# pcb_balun_bottom_notch.net
KiCad netlist of a schematic drawn in EAGLE
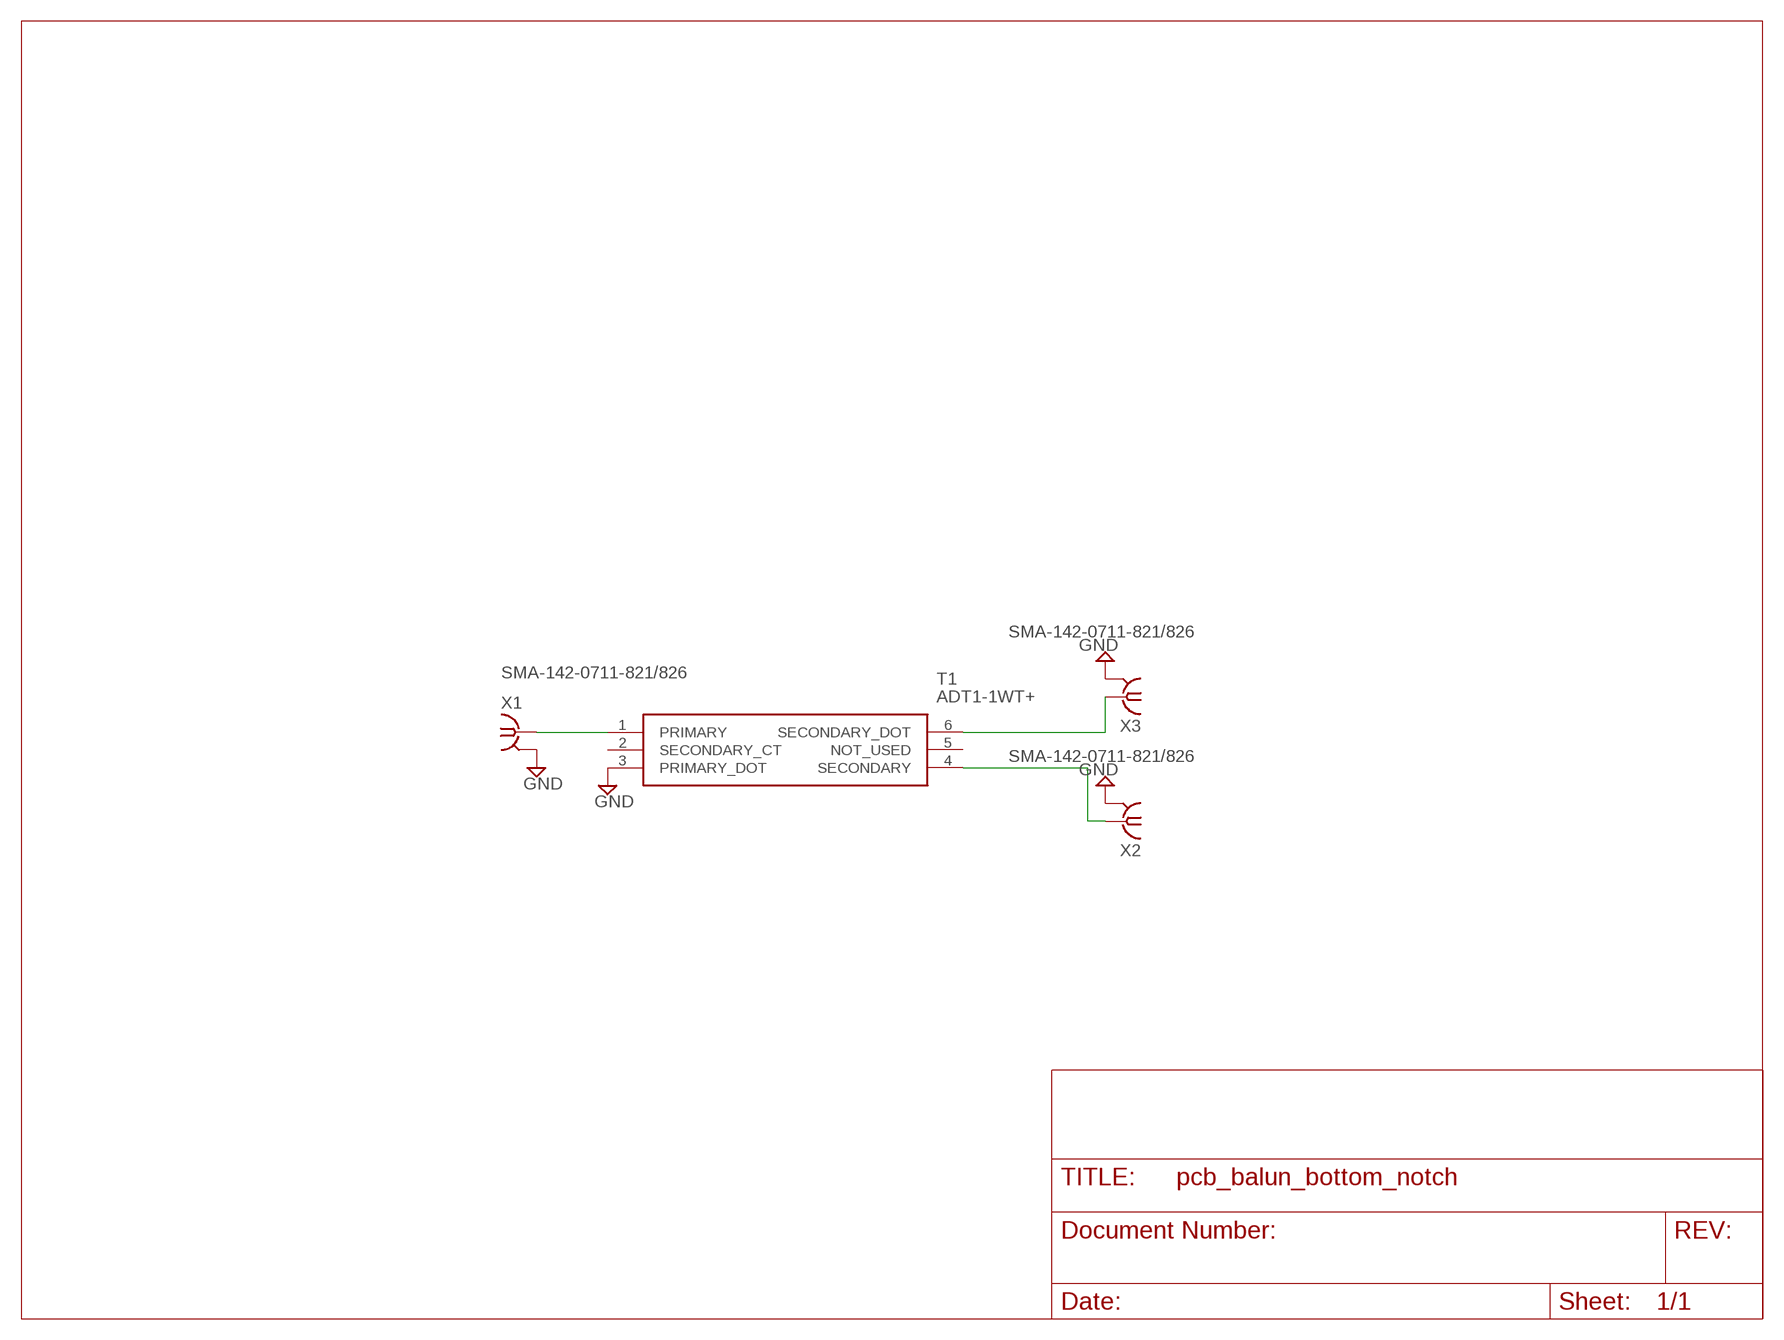
[diagram p0: schematic, sheet 1]

(export (version "E")
  (design (tool "Eeschema 10.0.6"))
  (components
    (comp (ref "T1")
      (value "ADT1-1WT+")
      (footprint "eagle-import:ADT11WT")
      (fields (field (name "MOUSER_PART_NUMBER") "139-ADT1-1WT"))
      (libsource (lib "eagle-import") (part "ADT1-1WT+"))
    )
    (comp (ref "X1")
      (value "SMA-142-0711-821/826")
      (footprint "eagle-import:J502-ND-142-0711-821_826")
      (fields (field (name "MF") "JOHNSON COMPONENTS") (field (name "MPN") "142-0711-821"))
      (libsource (lib "eagle-import") (part "SMA-142-0711-821/826"))
    )
    (comp (ref "X2")
      (value "SMA-142-0711-821/826")
      (footprint "eagle-import:J502-ND-142-0711-821_826")
      (fields (field (name "MF") "JOHNSON COMPONENTS") (field (name "MPN") "142-0711-821"))
      (libsource (lib "eagle-import") (part "SMA-142-0711-821/826"))
    )
    (comp (ref "X3")
      (value "SMA-142-0711-821/826")
      (footprint "eagle-import:J502-ND-142-0711-821_826")
      (fields (field (name "MF") "JOHNSON COMPONENTS") (field (name "MPN") "142-0711-821"))
      (libsource (lib "eagle-import") (part "SMA-142-0711-821/826"))
    )
  )
  (nets
    (net (code "1") (name "GND") (class "Default")
      (node (ref "T1") (pin "3") (pinfunction "PRIMARY_DOT_3") (pintype "bidirectional"))
      (node (ref "X1") (pin "G@1") (pinfunction "2_G@1") (pintype "passive"))
      (node (ref "X1") (pin "G@2") (pinfunction "2_G@2") (pintype "passive"))
      (node (ref "X1") (pin "G@3") (pinfunction "2_G@3") (pintype "passive"))
      (node (ref "X1") (pin "G@4") (pinfunction "2_G@4") (pintype "passive"))
      (node (ref "X2") (pin "G@1") (pinfunction "2_G@1") (pintype "passive"))
      (node (ref "X2") (pin "G@2") (pinfunction "2_G@2") (pintype "passive"))
      (node (ref "X2") (pin "G@3") (pinfunction "2_G@3") (pintype "passive"))
      (node (ref "X2") (pin "G@4") (pinfunction "2_G@4") (pintype "passive"))
      (node (ref "X3") (pin "G@1") (pinfunction "2_G@1") (pintype "passive"))
      (node (ref "X3") (pin "G@2") (pinfunction "2_G@2") (pintype "passive"))
      (node (ref "X3") (pin "G@3") (pinfunction "2_G@3") (pintype "passive"))
      (node (ref "X3") (pin "G@4") (pinfunction "2_G@4") (pintype "passive"))
    )
    (net (code "2") (name "Net-(T1-PRIMARY)") (class "Default")
      (node (ref "T1") (pin "1") (pinfunction "PRIMARY_1") (pintype "bidirectional"))
      (node (ref "X1") (pin "1") (pinfunction "1_1") (pintype "passive"))
    )
    (net (code "3") (name "Net-(T1-SECONDARY)") (class "Default")
      (node (ref "T1") (pin "4") (pinfunction "SECONDARY_4") (pintype "bidirectional"))
      (node (ref "X2") (pin "1") (pinfunction "1_1") (pintype "passive"))
    )
    (net (code "4") (name "Net-(T1-SECONDARY_DOT)") (class "Default")
      (node (ref "T1") (pin "6") (pinfunction "SECONDARY_DOT_6") (pintype "bidirectional"))
      (node (ref "X3") (pin "1") (pinfunction "1_1") (pintype "passive"))
    )
    (net (code "5") (name "unconnected-(T1-NOT_USED-Pad5)") (class "Default")
      (node (ref "T1") (pin "5") (pinfunction "NOT_USED_5") (pintype "bidirectional"))
    )
    (net (code "6") (name "unconnected-(T1-SECONDARY_CT-Pad2)") (class "Default")
      (node (ref "T1") (pin "2") (pinfunction "SECONDARY_CT_2") (pintype "bidirectional"))
    )
  )
)
